# power.net
KiCad netlist of a schematic drawn in Altium Designer
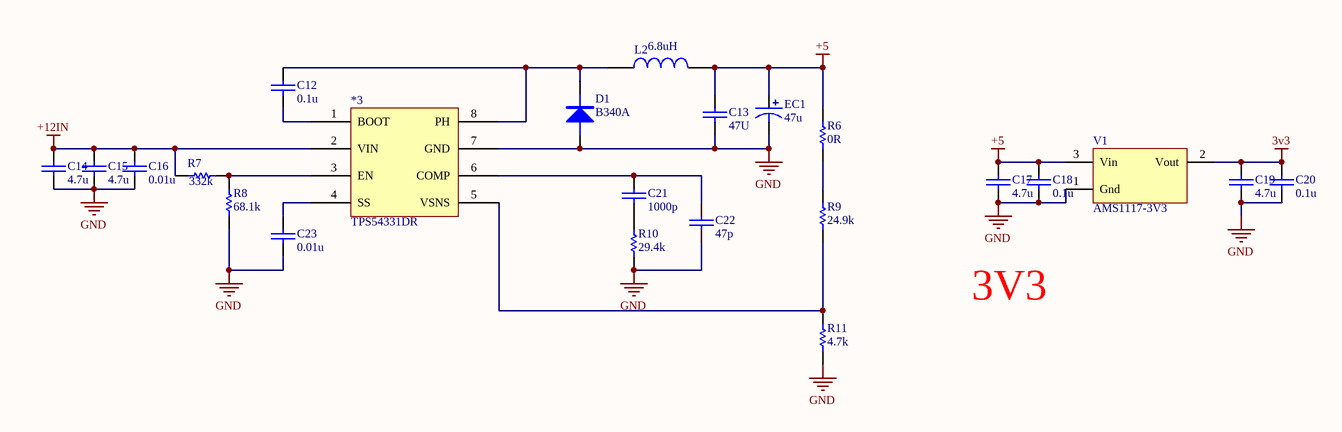
[diagram p0: power.SchDoc]

(export (version "E")
  (design (tool "Eeschema 10.0.6"))
  (components
    (comp (ref "*3")
      (value "TPS54331DR")
      (footprint "SOIC-8")
      (description "降压型DC-DC")
      (libsource (lib "0.03电源") (part "TPS54331DR"))
    )
    (comp (ref "C12")
      (value "0.1u")
      (footprint "0603C")
      (description "无极性电容")
      (libsource (lib "1.00-阻容感") (part "CAP"))
    )
    (comp (ref "C13")
      (value "47U")
      (footprint "0603C")
      (description "无极性电容")
      (libsource (lib "1.00-阻容感") (part "CAP"))
    )
    (comp (ref "C14")
      (value "4.7u")
      (footprint "0603C")
      (description "无极性电容")
      (libsource (lib "1.00-阻容感") (part "CAP"))
    )
    (comp (ref "C15")
      (value "4.7u")
      (footprint "0603C")
      (description "无极性电容")
      (libsource (lib "1.00-阻容感") (part "CAP"))
    )
    (comp (ref "C16")
      (value "0.01u")
      (footprint "0603C")
      (description "无极性电容")
      (libsource (lib "1.00-阻容感") (part "CAP"))
    )
    (comp (ref "C17")
      (value "4.7u")
      (footprint "0603C")
      (description "无极性电容")
      (libsource (lib "1.00-阻容感") (part "CAP"))
    )
    (comp (ref "C18")
      (value "0.1u")
      (footprint "0603C")
      (description "无极性电容")
      (libsource (lib "1.00-阻容感") (part "CAP"))
    )
    (comp (ref "C19")
      (value "4.7u")
      (footprint "0603C")
      (description "无极性电容")
      (libsource (lib "1.00-阻容感") (part "CAP"))
    )
    (comp (ref "C20")
      (value "0.1u")
      (footprint "0603C")
      (description "无极性电容")
      (libsource (lib "1.00-阻容感") (part "CAP"))
    )
    (comp (ref "C21")
      (value "1000p")
      (footprint "0603C")
      (description "无极性电容")
      (libsource (lib "1.00-阻容感") (part "CAP"))
    )
    (comp (ref "C22")
      (value "47p")
      (footprint "0603C")
      (description "无极性电容")
      (libsource (lib "1.00-阻容感") (part "CAP"))
    )
    (comp (ref "C23")
      (value "0.01u")
      (footprint "0603C")
      (description "无极性电容")
      (libsource (lib "1.00-阻容感") (part "CAP"))
    )
    (comp (ref "D1")
      (value "B340A")
      (footprint "SMA/DO-214AC")
      (description "普通二极管")
      (libsource (lib "2.00-二极管") (part "DIODE"))
    )
    (comp (ref "EC1")
      (value "47u")
      (footprint "SMD-EC6.3X6.3X10")
      (description "贴片电解电容")
      (libsource (lib "1.00-阻容感") (part "ECAP"))
    )
    (comp (ref "L2")
      (value "6.8uH")
      (footprint "L-SMD-0630")
      (description "INDUCTOR")
      (libsource (lib "1.00-阻容感") (part "L"))
    )
    (comp (ref "R6")
      (value "0R")
      (footprint "0603R")
      (description "电阻")
      (libsource (lib "1.00-阻容感") (part "RES"))
    )
    (comp (ref "R7")
      (value "332k")
      (footprint "0603R")
      (description "电阻")
      (libsource (lib "1.00-阻容感") (part "RES"))
    )
    (comp (ref "R8")
      (value "68.1k")
      (footprint "0603R")
      (description "电阻")
      (libsource (lib "1.00-阻容感") (part "RES"))
    )
    (comp (ref "R9")
      (value "24.9k")
      (footprint "0603R")
      (description "电阻")
      (libsource (lib "1.00-阻容感") (part "RES"))
    )
    (comp (ref "R10")
      (value "29.4k")
      (footprint "0603R")
      (description "电阻")
      (libsource (lib "1.00-阻容感") (part "RES"))
    )
    (comp (ref "R11")
      (value "4.7k")
      (footprint "0603R")
      (description "电阻")
      (libsource (lib "1.00-阻容感") (part "RES"))
    )
    (comp (ref "V1")
      (value "AMS1117-3V3")
      (footprint "SOT223_L")
      (description "LDO")
      (libsource (lib "0.03电源") (part "AMS1117"))
    )
  )
  (nets
    (net (code "1") (name "+5") (class "Default")
      (node (ref "C13") (pin "2") (pinfunction "2_2") (pintype "passive"))
      (node (ref "C17") (pin "2") (pinfunction "2_2") (pintype "passive"))
      (node (ref "C18") (pin "2") (pinfunction "2_2") (pintype "passive"))
      (node (ref "EC1") (pin "1") (pinfunction "1_1") (pintype "passive"))
      (node (ref "L2") (pin "2") (pinfunction "2_2") (pintype "passive"))
      (node (ref "R6") (pin "2") (pinfunction "2_2") (pintype "passive"))
      (node (ref "V1") (pin "3") (pinfunction "Vin_3") (pintype "passive"))
    )
    (net (code "2") (name "+12IN") (class "Default")
      (node (ref "*3") (pin "2") (pinfunction "VIN_2") (pintype "passive"))
      (node (ref "C14") (pin "2") (pinfunction "2_2") (pintype "passive"))
      (node (ref "C15") (pin "2") (pinfunction "2_2") (pintype "passive"))
      (node (ref "C16") (pin "2") (pinfunction "2_2") (pintype "passive"))
      (node (ref "R7") (pin "2") (pinfunction "2_2") (pintype "passive"))
    )
    (net (code "3") (name "3v3") (class "Default")
      (node (ref "C19") (pin "2") (pinfunction "2_2") (pintype "passive"))
      (node (ref "C20") (pin "2") (pinfunction "2_2") (pintype "passive"))
      (node (ref "V1") (pin "2") (pinfunction "Vout_2") (pintype "passive"))
    )
    (net (code "4") (name "GND") (class "Default")
      (node (ref "*3") (pin "7") (pinfunction "GND_7") (pintype "passive"))
      (node (ref "C13") (pin "1") (pinfunction "1_1") (pintype "passive"))
      (node (ref "C14") (pin "1") (pinfunction "1_1") (pintype "passive"))
      (node (ref "C15") (pin "1") (pinfunction "1_1") (pintype "passive"))
      (node (ref "C16") (pin "1") (pinfunction "1_1") (pintype "passive"))
      (node (ref "C17") (pin "1") (pinfunction "1_1") (pintype "passive"))
      (node (ref "C18") (pin "1") (pinfunction "1_1") (pintype "passive"))
      (node (ref "C19") (pin "1") (pinfunction "1_1") (pintype "passive"))
      (node (ref "C20") (pin "1") (pinfunction "1_1") (pintype "passive"))
      (node (ref "C22") (pin "1") (pinfunction "1_1") (pintype "passive"))
      (node (ref "C23") (pin "1") (pinfunction "1_1") (pintype "passive"))
      (node (ref "D1") (pin "A") (pinfunction "A_A") (pintype "passive"))
      (node (ref "EC1") (pin "2") (pinfunction "2_2") (pintype "passive"))
      (node (ref "R10") (pin "1") (pinfunction "1_1") (pintype "passive"))
      (node (ref "R11") (pin "1") (pinfunction "1_1") (pintype "passive"))
      (node (ref "R8") (pin "1") (pinfunction "1_1") (pintype "passive"))
      (node (ref "V1") (pin "1") (pinfunction "Gnd_1") (pintype "passive"))
    )
    (net (code "5") (name "Net-(*3-BOOT)") (class "Default")
      (node (ref "*3") (pin "1") (pinfunction "BOOT_1") (pintype "passive"))
      (node (ref "C12") (pin "1") (pinfunction "1_1") (pintype "passive"))
    )
    (net (code "6") (name "Net-(*3-COMP)") (class "Default")
      (node (ref "*3") (pin "6") (pinfunction "COMP_6") (pintype "passive"))
      (node (ref "C21") (pin "2") (pinfunction "2_2") (pintype "passive"))
      (node (ref "C22") (pin "2") (pinfunction "2_2") (pintype "passive"))
    )
    (net (code "7") (name "Net-(*3-EN)") (class "Default")
      (node (ref "*3") (pin "3") (pinfunction "EN_3") (pintype "passive"))
      (node (ref "R7") (pin "1") (pinfunction "1_1") (pintype "passive"))
      (node (ref "R8") (pin "2") (pinfunction "2_2") (pintype "passive"))
    )
    (net (code "8") (name "Net-(*3-PH)") (class "Default")
      (node (ref "*3") (pin "8") (pinfunction "PH_8") (pintype "passive"))
      (node (ref "C12") (pin "2") (pinfunction "2_2") (pintype "passive"))
      (node (ref "D1") (pin "K") (pinfunction "K_K") (pintype "passive"))
      (node (ref "L2") (pin "1") (pinfunction "1_1") (pintype "passive"))
    )
    (net (code "9") (name "Net-(*3-SS)") (class "Default")
      (node (ref "*3") (pin "4") (pinfunction "SS_4") (pintype "passive"))
      (node (ref "C23") (pin "2") (pinfunction "2_2") (pintype "passive"))
    )
    (net (code "10") (name "Net-(*3-VSNS)") (class "Default")
      (node (ref "*3") (pin "5") (pinfunction "VSNS_5") (pintype "passive"))
      (node (ref "R11") (pin "2") (pinfunction "2_2") (pintype "passive"))
      (node (ref "R9") (pin "1") (pinfunction "1_1") (pintype "passive"))
    )
    (net (code "11") (name "Net-(C21-Pad1)") (class "Default")
      (node (ref "C21") (pin "1") (pinfunction "1_1") (pintype "passive"))
      (node (ref "R10") (pin "2") (pinfunction "2_2") (pintype "passive"))
    )
    (net (code "12") (name "Net-(R6-Pad1)") (class "Default")
      (node (ref "R6") (pin "1") (pinfunction "1_1") (pintype "passive"))
      (node (ref "R9") (pin "2") (pinfunction "2_2") (pintype "passive"))
    )
  )
)
